# Shematich_v1.net
KiCad netlist of a schematic drawn in EAGLE
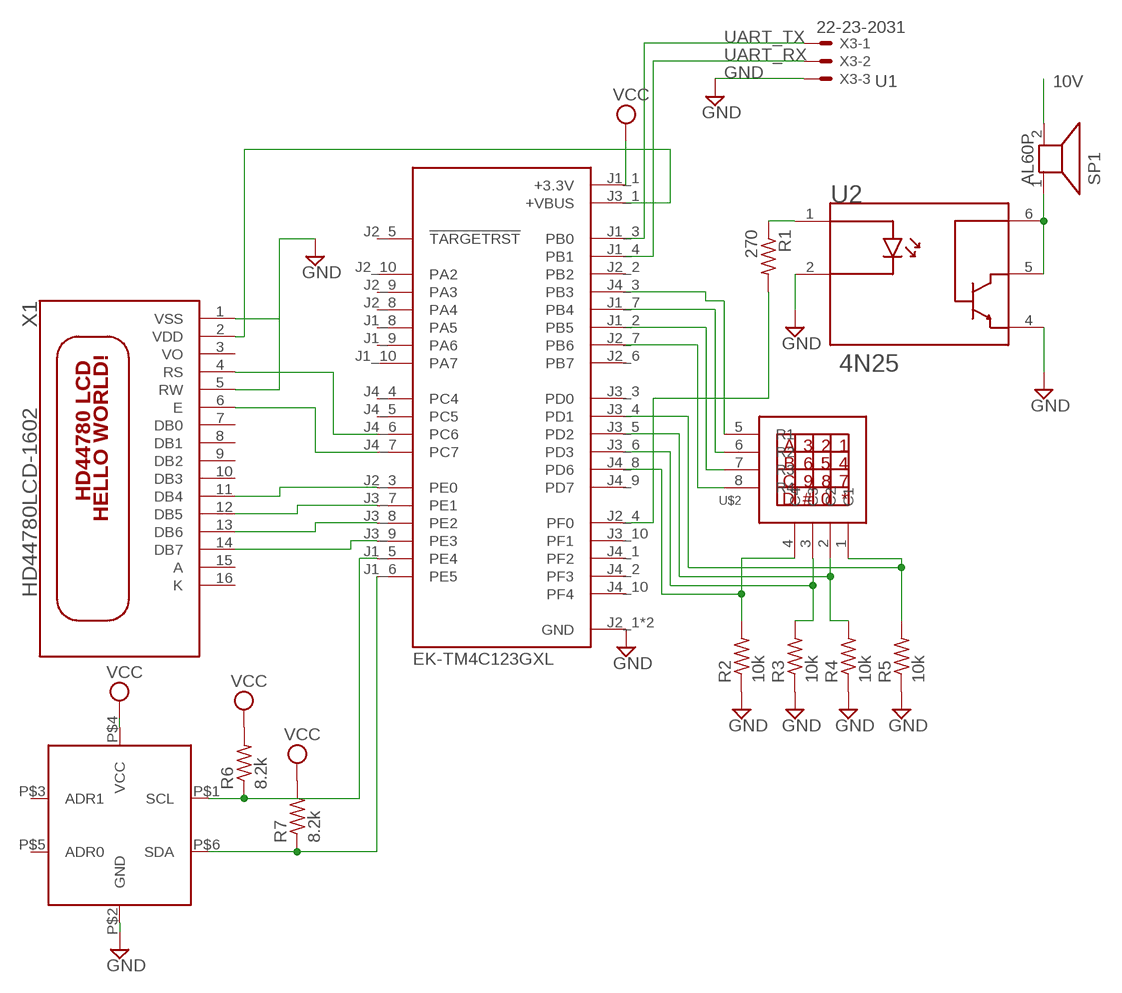
[diagram p0: schematic, sheet 1]

(export (version "E")
  (design (tool "Eeschema 10.0.6"))
  (components
    (comp (ref "R1")
      (value "270")
      (footprint "eagle-import:0204_7")
      (libsource (lib "eagle-import") (part "R-US_0204/7"))
    )
    (comp (ref "R2")
      (value "10k")
      (footprint "eagle-import:0204_7")
      (libsource (lib "eagle-import") (part "R-US_0204/7"))
    )
    (comp (ref "R3")
      (value "10k")
      (footprint "eagle-import:0204_7")
      (libsource (lib "eagle-import") (part "R-US_0204/7"))
    )
    (comp (ref "R4")
      (value "10k")
      (footprint "eagle-import:0204_7")
      (libsource (lib "eagle-import") (part "R-US_0204/7"))
    )
    (comp (ref "R5")
      (value "10k")
      (footprint "eagle-import:0204_7")
      (libsource (lib "eagle-import") (part "R-US_0204/7"))
    )
    (comp (ref "R6")
      (value "8.2k")
      (footprint "eagle-import:0204_7")
      (libsource (lib "eagle-import") (part "R-US_0204/7"))
    )
    (comp (ref "R7")
      (value "8.2k")
      (footprint "eagle-import:0204_7")
      (libsource (lib "eagle-import") (part "R-US_0204/7"))
    )
    (comp (ref "SP1")
      (value "AL60P")
      (footprint "eagle-import:AL60P")
      (libsource (lib "eagle-import") (part "AL60P"))
    )
    (comp (ref "U$1")
      (value "TMP100")
      (footprint "eagle-import:SOT23-6")
      (libsource (lib "eagle-import") (part "TMP100"))
    )
    (comp (ref "U$2")
      (value "KEYPAD4X4")
      (footprint "eagle-import:KEYPAD4X4")
      (libsource (lib "eagle-import") (part "KEYPAD4X4"))
    )
    (comp (ref "U1")
      (value "EK-TM4C123GXL")
      (footprint "eagle-import:MODULE_EK-TM4C123GXL")
      (fields (field (name "MF") "Texas Instruments"))
      (libsource (lib "eagle-import") (part "EK-TM4C123GXL"))
    )
    (comp (ref "U2")
      (value "4N25")
      (footprint "eagle-import:DIP762W50P254L712H400Q6N")
      (fields (field (name "MF") "Vishay Semiconductor"))
      (libsource (lib "eagle-import") (part "4N25"))
    )
    (comp (ref "X1")
      (value "HD44780LCD-1602")
      (footprint "eagle-import:LCD1602")
      (libsource (lib "eagle-import") (part "HD44780LCD-1602"))
    )
    (comp (ref "X3")
      (value "22-23-2031")
      (footprint "eagle-import:22-23-2031")
      (fields (field (name "MF") "MOLEX"))
      (libsource (lib "eagle-import") (part "22-23-2031"))
    )
  )
  (nets
    (net (code "1") (name "/10V") (class "Default")
      (node (ref "SP1") (pin "2") (pinfunction "2_2") (pintype "passive"))
    )
    (net (code "2") (name "/UART_RX") (class "Default")
      (node (ref "U1") (pin "J1_4") (pinfunction "PB1_J1_4") (pintype "bidirectional"))
      (node (ref "X3") (pin "2") (pinfunction "S_2") (pintype "passive"))
    )
    (net (code "3") (name "/UART_TX") (class "Default")
      (node (ref "U1") (pin "J1_3") (pinfunction "PB0_J1_3") (pintype "bidirectional"))
      (node (ref "X3") (pin "1") (pinfunction "S_1") (pintype "passive"))
    )
    (net (code "4") (name "GND") (class "Default")
      (node (ref "R2") (pin "1") (pinfunction "1_1") (pintype "passive"))
      (node (ref "R3") (pin "1") (pinfunction "1_1") (pintype "passive"))
      (node (ref "R4") (pin "1") (pinfunction "1_1") (pintype "passive"))
      (node (ref "R5") (pin "1") (pinfunction "1_1") (pintype "passive"))
      (node (ref "U$1") (pin "P$2") (pinfunction "GND_P$2") (pintype "power_in"))
      (node (ref "U1") (pin "J2_1") (pinfunction "GND_J2_1") (pintype "power_in"))
      (node (ref "U1") (pin "J3_2") (pinfunction "GND_J3_2") (pintype "power_in"))
      (node (ref "U2") (pin "2") (pinfunction "K_2") (pintype "passive"))
      (node (ref "U2") (pin "4") (pinfunction "E_4") (pintype "passive"))
      (node (ref "X1") (pin "1") (pinfunction "VSS_1") (pintype "power_in"))
      (node (ref "X1") (pin "5") (pinfunction "RW_5") (pintype "input"))
      (node (ref "X3") (pin "3") (pinfunction "S_3") (pintype "passive"))
    )
    (net (code "5") (name "Net-(U$1-SCL)") (class "Default")
      (node (ref "R6") (pin "1") (pinfunction "1_1") (pintype "passive"))
      (node (ref "U$1") (pin "P$1") (pinfunction "SCL_P$1") (pintype "bidirectional"))
      (node (ref "U1") (pin "J1_5") (pinfunction "PE4_J1_5") (pintype "bidirectional"))
    )
    (net (code "6") (name "Net-(U$1-SDA)") (class "Default")
      (node (ref "R7") (pin "1") (pinfunction "1_1") (pintype "passive"))
      (node (ref "U$1") (pin "P$6") (pinfunction "SDA_P$6") (pintype "bidirectional"))
      (node (ref "U1") (pin "J1_6") (pinfunction "PE5_J1_6") (pintype "bidirectional"))
    )
    (net (code "7") (name "Net-(U$2-C1)") (class "Default")
      (node (ref "R5") (pin "2") (pinfunction "2_2") (pintype "passive"))
      (node (ref "U$2") (pin "1") (pinfunction "C1_1") (pintype "bidirectional"))
      (node (ref "U1") (pin "J3_4") (pinfunction "PD1_J3_4") (pintype "bidirectional"))
    )
    (net (code "8") (name "Net-(U$2-C2)") (class "Default")
      (node (ref "R4") (pin "2") (pinfunction "2_2") (pintype "passive"))
      (node (ref "U$2") (pin "2") (pinfunction "C2_2") (pintype "bidirectional"))
      (node (ref "U1") (pin "J3_5") (pinfunction "PD2_J3_5") (pintype "bidirectional"))
    )
    (net (code "9") (name "Net-(U$2-C3)") (class "Default")
      (node (ref "R3") (pin "2") (pinfunction "2_2") (pintype "passive"))
      (node (ref "U$2") (pin "3") (pinfunction "C3_3") (pintype "bidirectional"))
      (node (ref "U1") (pin "J3_6") (pinfunction "PD3_J3_6") (pintype "bidirectional"))
    )
    (net (code "10") (name "Net-(U$2-C4)") (class "Default")
      (node (ref "R2") (pin "2") (pinfunction "2_2") (pintype "passive"))
      (node (ref "U$2") (pin "4") (pinfunction "C4_4") (pintype "bidirectional"))
      (node (ref "U1") (pin "J4_8") (pinfunction "PD6_J4_8") (pintype "bidirectional"))
    )
    (net (code "11") (name "Net-(U$2-R1)") (class "Default")
      (node (ref "U$2") (pin "5") (pinfunction "R1_5") (pintype "bidirectional"))
      (node (ref "U1") (pin "J4_3") (pinfunction "PB3_J4_3") (pintype "bidirectional"))
    )
    (net (code "12") (name "Net-(U$2-R2)") (class "Default")
      (node (ref "U$2") (pin "6") (pinfunction "R2_6") (pintype "bidirectional"))
      (node (ref "U1") (pin "J1_7") (pinfunction "PB4_J1_7") (pintype "bidirectional"))
    )
    (net (code "13") (name "Net-(U$2-R3)") (class "Default")
      (node (ref "U$2") (pin "7") (pinfunction "R3_7") (pintype "bidirectional"))
      (node (ref "U1") (pin "J1_2") (pinfunction "PB5_J1_2") (pintype "bidirectional"))
    )
    (net (code "14") (name "Net-(U$2-R4)") (class "Default")
      (node (ref "U$2") (pin "8") (pinfunction "R4_8") (pintype "bidirectional"))
      (node (ref "U1") (pin "J2_7") (pinfunction "PB6_J2_7") (pintype "bidirectional"))
    )
    (net (code "15") (name "Net-(U1-+VBUS)") (class "Default")
      (node (ref "U1") (pin "J3_1") (pinfunction "+VBUS_J3_1") (pintype "power_in"))
      (node (ref "X1") (pin "2") (pinfunction "VDD_2") (pintype "power_in"))
    )
    (net (code "16") (name "Net-(U1-PC6)") (class "Default")
      (node (ref "U1") (pin "J4_6") (pinfunction "PC6_J4_6") (pintype "bidirectional"))
      (node (ref "X1") (pin "4") (pinfunction "RS_4") (pintype "input"))
    )
    (net (code "17") (name "Net-(U1-PC7)") (class "Default")
      (node (ref "U1") (pin "J4_7") (pinfunction "PC7_J4_7") (pintype "bidirectional"))
      (node (ref "X1") (pin "6") (pinfunction "E_6") (pintype "input"))
    )
    (net (code "18") (name "Net-(U1-PE0)") (class "Default")
      (node (ref "U1") (pin "J2_3") (pinfunction "PE0_J2_3") (pintype "bidirectional"))
      (node (ref "X1") (pin "11") (pinfunction "DB4_11") (pintype "bidirectional"))
    )
    (net (code "19") (name "Net-(U1-PE1)") (class "Default")
      (node (ref "U1") (pin "J3_7") (pinfunction "PE1_J3_7") (pintype "bidirectional"))
      (node (ref "X1") (pin "12") (pinfunction "DB5_12") (pintype "bidirectional"))
    )
    (net (code "20") (name "Net-(U1-PE2)") (class "Default")
      (node (ref "U1") (pin "J3_8") (pinfunction "PE2_J3_8") (pintype "bidirectional"))
      (node (ref "X1") (pin "13") (pinfunction "DB6_13") (pintype "bidirectional"))
    )
    (net (code "21") (name "Net-(U1-PE3)") (class "Default")
      (node (ref "U1") (pin "J3_9") (pinfunction "PE3_J3_9") (pintype "bidirectional"))
      (node (ref "X1") (pin "14") (pinfunction "DB7_14") (pintype "bidirectional"))
    )
    (net (code "22") (name "Net-(U1-PF0)") (class "Default")
      (node (ref "R1") (pin "2") (pinfunction "2_2") (pintype "passive"))
      (node (ref "U1") (pin "J2_4") (pinfunction "PF0_J2_4") (pintype "bidirectional"))
    )
    (net (code "23") (name "Net-(U2-A)") (class "Default")
      (node (ref "R1") (pin "1") (pinfunction "1_1") (pintype "passive"))
      (node (ref "U2") (pin "1") (pinfunction "A_1") (pintype "passive"))
    )
    (net (code "24") (name "Net-(U2-B)") (class "Default")
      (node (ref "SP1") (pin "1") (pinfunction "1_1") (pintype "passive"))
      (node (ref "U2") (pin "5") (pinfunction "C_5") (pintype "passive"))
      (node (ref "U2") (pin "6") (pinfunction "B_6") (pintype "passive"))
    )
    (net (code "25") (name "VCC") (class "Default")
      (node (ref "R6") (pin "2") (pinfunction "2_2") (pintype "passive"))
      (node (ref "R7") (pin "2") (pinfunction "2_2") (pintype "passive"))
      (node (ref "U$1") (pin "P$4") (pinfunction "VCC_P$4") (pintype "power_in"))
      (node (ref "U1") (pin "J1_1") (pinfunction "+3.3V_J1_1") (pintype "power_in"))
    )
    (net (code "26") (name "unconnected-(U$1-ADR0-PadP$5)") (class "Default")
      (node (ref "U$1") (pin "P$5") (pinfunction "ADR0_P$5") (pintype "bidirectional"))
    )
    (net (code "27") (name "unconnected-(U$1-ADR1-PadP$3)") (class "Default")
      (node (ref "U$1") (pin "P$3") (pinfunction "ADR1_P$3") (pintype "bidirectional"))
    )
    (net (code "28") (name "unconnected-(U1-PA2-PadJ2_10)") (class "Default")
      (node (ref "U1") (pin "J2_10") (pinfunction "PA2_J2_10") (pintype "bidirectional"))
    )
    (net (code "29") (name "unconnected-(U1-PA3-PadJ2_9)") (class "Default")
      (node (ref "U1") (pin "J2_9") (pinfunction "PA3_J2_9") (pintype "bidirectional"))
    )
    (net (code "30") (name "unconnected-(U1-PA4-PadJ2_8)") (class "Default")
      (node (ref "U1") (pin "J2_8") (pinfunction "PA4_J2_8") (pintype "bidirectional"))
    )
    (net (code "31") (name "unconnected-(U1-PA5-PadJ1_8)") (class "Default")
      (node (ref "U1") (pin "J1_8") (pinfunction "PA5_J1_8") (pintype "bidirectional"))
    )
    (net (code "32") (name "unconnected-(U1-PA6-PadJ1_9)") (class "Default")
      (node (ref "U1") (pin "J1_9") (pinfunction "PA6_J1_9") (pintype "bidirectional"))
    )
    (net (code "33") (name "unconnected-(U1-PA7-PadJ1_10)") (class "Default")
      (node (ref "U1") (pin "J1_10") (pinfunction "PA7_J1_10") (pintype "bidirectional"))
    )
    (net (code "34") (name "unconnected-(U1-PB2-PadJ2_2)") (class "Default")
      (node (ref "U1") (pin "J2_2") (pinfunction "PB2_J2_2") (pintype "bidirectional"))
    )
    (net (code "35") (name "unconnected-(U1-PB7-PadJ2_6)") (class "Default")
      (node (ref "U1") (pin "J2_6") (pinfunction "PB7_J2_6") (pintype "bidirectional"))
    )
    (net (code "36") (name "unconnected-(U1-PC4-PadJ4_4)") (class "Default")
      (node (ref "U1") (pin "J4_4") (pinfunction "PC4_J4_4") (pintype "bidirectional"))
    )
    (net (code "37") (name "unconnected-(U1-PC5-PadJ4_5)") (class "Default")
      (node (ref "U1") (pin "J4_5") (pinfunction "PC5_J4_5") (pintype "bidirectional"))
    )
    (net (code "38") (name "unconnected-(U1-PD0-PadJ3_3)") (class "Default")
      (node (ref "U1") (pin "J3_3") (pinfunction "PD0_J3_3") (pintype "bidirectional"))
    )
    (net (code "39") (name "unconnected-(U1-PD7-PadJ4_9)") (class "Default")
      (node (ref "U1") (pin "J4_9") (pinfunction "PD7_J4_9") (pintype "bidirectional"))
    )
    (net (code "40") (name "unconnected-(U1-PF1-PadJ3_10)") (class "Default")
      (node (ref "U1") (pin "J3_10") (pinfunction "PF1_J3_10") (pintype "bidirectional"))
    )
    (net (code "41") (name "unconnected-(U1-PF2-PadJ4_1)") (class "Default")
      (node (ref "U1") (pin "J4_1") (pinfunction "PF2_J4_1") (pintype "bidirectional"))
    )
    (net (code "42") (name "unconnected-(U1-PF3-PadJ4_2)") (class "Default")
      (node (ref "U1") (pin "J4_2") (pinfunction "PF3_J4_2") (pintype "bidirectional"))
    )
    (net (code "43") (name "unconnected-(U1-PF4-PadJ4_10)") (class "Default")
      (node (ref "U1") (pin "J4_10") (pinfunction "PF4_J4_10") (pintype "bidirectional"))
    )
    (net (code "44") (name "unconnected-(U1-~{TARGETRST}-PadJ2_5)") (class "Default")
      (node (ref "U1") (pin "J2_5") (pinfunction "~{TARGETRST}_J2_5") (pintype "input"))
    )
    (net (code "45") (name "unconnected-(X1-A-Pad15)") (class "Default")
      (node (ref "X1") (pin "15") (pinfunction "A_15") (pintype "input"))
    )
    (net (code "46") (name "unconnected-(X1-DB0-Pad7)") (class "Default")
      (node (ref "X1") (pin "7") (pinfunction "DB0_7") (pintype "bidirectional"))
    )
    (net (code "47") (name "unconnected-(X1-DB1-Pad8)") (class "Default")
      (node (ref "X1") (pin "8") (pinfunction "DB1_8") (pintype "bidirectional"))
    )
    (net (code "48") (name "unconnected-(X1-DB2-Pad9)") (class "Default")
      (node (ref "X1") (pin "9") (pinfunction "DB2_9") (pintype "bidirectional"))
    )
    (net (code "49") (name "unconnected-(X1-DB3-Pad10)") (class "Default")
      (node (ref "X1") (pin "10") (pinfunction "DB3_10") (pintype "bidirectional"))
    )
    (net (code "50") (name "unconnected-(X1-K-Pad16)") (class "Default")
      (node (ref "X1") (pin "16") (pinfunction "K_16") (pintype "input"))
    )
    (net (code "51") (name "unconnected-(X1-VO-Pad3)") (class "Default")
      (node (ref "X1") (pin "3") (pinfunction "VO_3") (pintype "input"))
    )
  )
)
